# Filter-15.net
KiCad netlist of a schematic drawn in Altium Designer
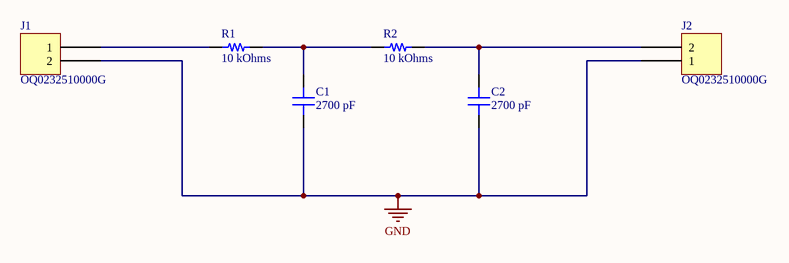
[diagram p0: Filter-15.SchDoc]

(export (version "E")
  (design (tool "Eeschema 10.0.6"))
  (components
    (comp (ref "C1")
      (value "2700 pF")
      (footprint "CAP 0603_1608")
      (description "CAP CER 2700PF 25V NP0 0603")
      (fields (field (name "PART NUMBER") "C0603C272F3GAC7867") (field (name "MANUFACTURER") "KEMET"))
      (libsource (lib "Celestial Altium Library - altium_library") (part "Capacitor"))
    )
    (comp (ref "C2")
      (value "2700 pF")
      (footprint "CAP 0603_1608")
      (description "CAP CER 2700PF 25V NP0 0603")
      (fields (field (name "PART NUMBER") "C0603C272F3GAC7867") (field (name "MANUFACTURER") "KEMET"))
      (libsource (lib "Celestial Altium Library - altium_library") (part "Capacitor"))
    )
    (comp (ref "J1")
      (value "OQ0232510000G")
      (footprint "FCI 06-381-2PIN")
      (description "TERM BLOCK HDR 2POS 90DEG 3.81MM")
      (fields (field (name "MANUFACTURER") "Amphenol Anytek"))
      (libsource (lib "Celestial Altium Library - altium_library") (part "2 Pin"))
    )
    (comp (ref "J2")
      (value "OQ0232510000G")
      (footprint "FCI 06-381-2PIN")
      (description "TERM BLOCK HDR 2POS 90DEG 3.81MM")
      (fields (field (name "MANUFACTURER") "Amphenol Anytek"))
      (libsource (lib "") (part "2 Pin_1"))
    )
    (comp (ref "R1")
      (value "10 kOhms")
      (footprint "RES 0603_1608")
      (description "RES 10K OHM 0.1% 1/16W 0603")
      (fields
        (field (name "PART NUMBER") "RNCS0603BKE10K0")
        (field (name "MANUFACTURER") "Stackpole Electronics Inc")
      )
      (libsource (lib "Celestial Altium Library - altium_library") (part "Resistor"))
    )
    (comp (ref "R2")
      (value "10 kOhms")
      (footprint "RES 0603_1608")
      (description "RES 10K OHM 0.1% 1/16W 0603")
      (fields
        (field (name "PART NUMBER") "RNCS0603BKE10K0")
        (field (name "MANUFACTURER") "Stackpole Electronics Inc")
      )
      (libsource (lib "Celestial Altium Library - altium_library") (part "Resistor"))
    )
  )
  (nets
    (net (code "1") (name "GND") (class "Default")
      (node (ref "C1") (pin "1") (pinfunction "1_1") (pintype "passive"))
      (node (ref "C2") (pin "1") (pinfunction "1_1") (pintype "passive"))
      (node (ref "J1") (pin "2") (pinfunction "2_2") (pintype "passive"))
      (node (ref "J2") (pin "1") (pinfunction "1_1") (pintype "passive"))
    )
    (net (code "2") (name "Net-(C1-Pad2)") (class "Default")
      (node (ref "C1") (pin "2") (pinfunction "2_2") (pintype "passive"))
      (node (ref "R1") (pin "2") (pinfunction "2_2") (pintype "passive"))
      (node (ref "R2") (pin "1") (pinfunction "1_1") (pintype "passive"))
    )
    (net (code "3") (name "Net-(C2-Pad2)") (class "Default")
      (node (ref "C2") (pin "2") (pinfunction "2_2") (pintype "passive"))
      (node (ref "J2") (pin "2") (pinfunction "2_2") (pintype "passive"))
      (node (ref "R2") (pin "2") (pinfunction "2_2") (pintype "passive"))
    )
    (net (code "4") (name "Net-(J1-Pad1)") (class "Default")
      (node (ref "J1") (pin "1") (pinfunction "1_1") (pintype "passive"))
      (node (ref "R1") (pin "1") (pinfunction "1_1") (pintype "passive"))
    )
  )
)
